# PotyEEG_v9.net
KiCad netlist of a schematic drawn in EAGLE
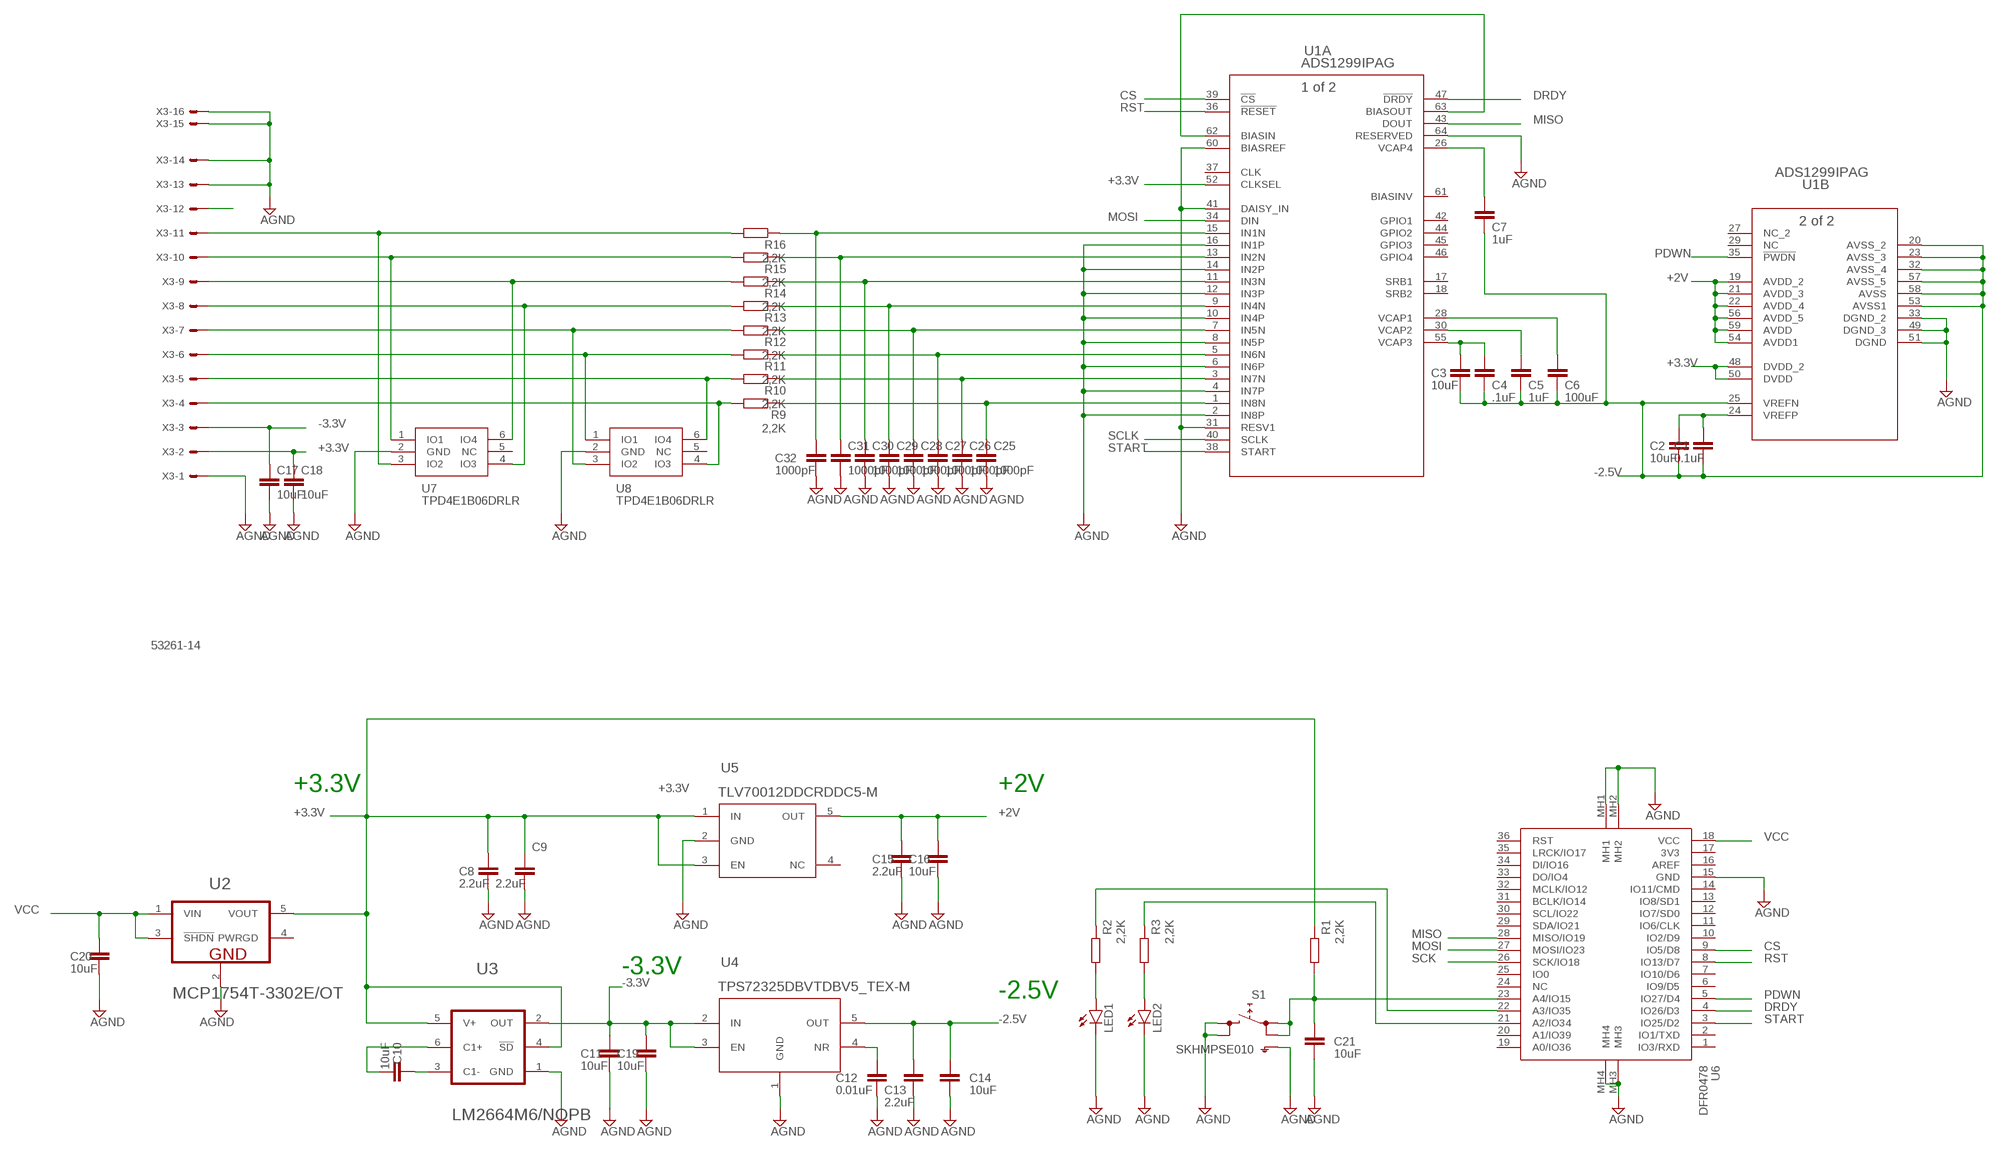
[diagram p0: schematic, sheet 1]

(export (version "E")
  (design (tool "Eeschema 10.0.6"))
  (components
    (comp (ref "C1")
      (value "0.1uF")
      (footprint "eagle-import:C0805K")
      (libsource (lib "eagle-import") (part "C-EUC0805K"))
    )
    (comp (ref "C2")
      (value "10uF")
      (footprint "eagle-import:C0805K")
      (libsource (lib "eagle-import") (part "C-EUC0805K"))
    )
    (comp (ref "C3")
      (value "10uF")
      (footprint "eagle-import:C0805K")
      (libsource (lib "eagle-import") (part "C-EUC0805K"))
    )
    (comp (ref "C4")
      (value ".1uF")
      (footprint "eagle-import:C0805K")
      (libsource (lib "eagle-import") (part "C-EUC0805K"))
    )
    (comp (ref "C5")
      (value "1uF")
      (footprint "eagle-import:C0805K")
      (libsource (lib "eagle-import") (part "C-EUC0805K"))
    )
    (comp (ref "C6")
      (value "100uF")
      (footprint "eagle-import:C0805K")
      (libsource (lib "eagle-import") (part "C-EUC0805K"))
    )
    (comp (ref "C7")
      (value "1uF")
      (footprint "eagle-import:C0805K")
      (libsource (lib "eagle-import") (part "C-EUC0805K"))
    )
    (comp (ref "C8")
      (value "2.2uF")
      (footprint "eagle-import:C0805K")
      (libsource (lib "eagle-import") (part "C-EUC0805K"))
    )
    (comp (ref "C9")
      (value "2.2uF")
      (footprint "eagle-import:C0805K")
      (libsource (lib "eagle-import") (part "C-EUC0805K"))
    )
    (comp (ref "C10")
      (value "10uF")
      (footprint "eagle-import:C0805K")
      (libsource (lib "eagle-import") (part "C-EUC0805K"))
    )
    (comp (ref "C11")
      (value "10uF")
      (footprint "eagle-import:C0805K")
      (libsource (lib "eagle-import") (part "C-EUC0805K"))
    )
    (comp (ref "C12")
      (value "0.01uF")
      (footprint "eagle-import:C0805K")
      (libsource (lib "eagle-import") (part "C-EUC0805K"))
    )
    (comp (ref "C13")
      (value "2.2uF")
      (footprint "eagle-import:C0805K")
      (libsource (lib "eagle-import") (part "C-EUC0805K"))
    )
    (comp (ref "C14")
      (value "10uF")
      (footprint "eagle-import:C0805K")
      (libsource (lib "eagle-import") (part "C-EUC0805K"))
    )
    (comp (ref "C15")
      (value "2.2uF")
      (footprint "eagle-import:C0805K")
      (libsource (lib "eagle-import") (part "C-EUC0805K"))
    )
    (comp (ref "C16")
      (value "10uF")
      (footprint "eagle-import:C0805K")
      (libsource (lib "eagle-import") (part "C-EUC0805K"))
    )
    (comp (ref "C17")
      (value "10uF")
      (footprint "eagle-import:C0603")
      (libsource (lib "eagle-import") (part "C-EUC0603"))
    )
    (comp (ref "C18")
      (value "10uF")
      (footprint "eagle-import:C0603")
      (libsource (lib "eagle-import") (part "C-EUC0603"))
    )
    (comp (ref "C19")
      (value "10uF")
      (footprint "eagle-import:C0805K")
      (libsource (lib "eagle-import") (part "C-EUC0805K"))
    )
    (comp (ref "C20")
      (value "10uF")
      (footprint "eagle-import:C0805K")
      (libsource (lib "eagle-import") (part "C-EUC0805K"))
    )
    (comp (ref "C21")
      (value "10uF")
      (footprint "eagle-import:C0805K")
      (libsource (lib "eagle-import") (part "C-EUC0805K"))
    )
    (comp (ref "C25")
      (value "1000pF")
      (footprint "eagle-import:C0603")
      (libsource (lib "eagle-import") (part "C-EUC0603"))
    )
    (comp (ref "C26")
      (value "1000pF")
      (footprint "eagle-import:C0603")
      (libsource (lib "eagle-import") (part "C-EUC0603"))
    )
    (comp (ref "C27")
      (value "1000pF")
      (footprint "eagle-import:C0603")
      (libsource (lib "eagle-import") (part "C-EUC0603"))
    )
    (comp (ref "C28")
      (value "1000pF")
      (footprint "eagle-import:C0603")
      (libsource (lib "eagle-import") (part "C-EUC0603"))
    )
    (comp (ref "C29")
      (value "1000pF")
      (footprint "eagle-import:C0603")
      (libsource (lib "eagle-import") (part "C-EUC0603"))
    )
    (comp (ref "C30")
      (value "1000pF")
      (footprint "eagle-import:C0603")
      (libsource (lib "eagle-import") (part "C-EUC0603"))
    )
    (comp (ref "C31")
      (value "1000pF")
      (footprint "eagle-import:C0603")
      (libsource (lib "eagle-import") (part "C-EUC0603"))
    )
    (comp (ref "C32")
      (value "1000pF")
      (footprint "eagle-import:C0603")
      (libsource (lib "eagle-import") (part "C-EUC0603"))
    )
    (comp (ref "LED1")
      (value "LEDSML0805")
      (footprint "eagle-import:SML0805")
      (libsource (lib "eagle-import") (part "LEDSML0805"))
    )
    (comp (ref "LED2")
      (value "LEDSML0805")
      (footprint "eagle-import:SML0805")
      (libsource (lib "eagle-import") (part "LEDSML0805"))
    )
    (comp (ref "R1")
      (value "2,2K")
      (footprint "eagle-import:R0603")
      (libsource (lib "eagle-import") (part "R-EU_R0603"))
    )
    (comp (ref "R2")
      (value "2,2K")
      (footprint "eagle-import:R0603")
      (libsource (lib "eagle-import") (part "R-EU_R0603"))
    )
    (comp (ref "R3")
      (value "2,2K")
      (footprint "eagle-import:R0603")
      (libsource (lib "eagle-import") (part "R-EU_R0603"))
    )
    (comp (ref "R9")
      (value "2,2K")
      (footprint "eagle-import:R0603")
      (libsource (lib "eagle-import") (part "R-EU_R0603"))
    )
    (comp (ref "R10")
      (value "2,2K")
      (footprint "eagle-import:R0603")
      (libsource (lib "eagle-import") (part "R-EU_R0603"))
    )
    (comp (ref "R11")
      (value "2,2K")
      (footprint "eagle-import:R0603")
      (libsource (lib "eagle-import") (part "R-EU_R0603"))
    )
    (comp (ref "R12")
      (value "2,2K")
      (footprint "eagle-import:R0603")
      (libsource (lib "eagle-import") (part "R-EU_R0603"))
    )
    (comp (ref "R13")
      (value "2,2K")
      (footprint "eagle-import:R0603")
      (libsource (lib "eagle-import") (part "R-EU_R0603"))
    )
    (comp (ref "R14")
      (value "2,2K")
      (footprint "eagle-import:R0603")
      (libsource (lib "eagle-import") (part "R-EU_R0603"))
    )
    (comp (ref "R15")
      (value "2,2K")
      (footprint "eagle-import:R0603")
      (libsource (lib "eagle-import") (part "R-EU_R0603"))
    )
    (comp (ref "R16")
      (value "2,2K")
      (footprint "eagle-import:R0603")
      (libsource (lib "eagle-import") (part "R-EU_R0603"))
    )
    (comp (ref "S1")
      (value "SKHMPSE010")
      (footprint "eagle-import:SKHMPXE010")
      (libsource (lib "eagle-import") (part "SKHMPE010S"))
    )
    (comp (ref "U1")
      (value "ADS1299IPAG")
      (footprint "eagle-import:PAG64_TEX")
      (libsource (lib "eagle-import") (part "ADS1299IPAG"))
    )
    (comp (ref "U2")
      (value "MICROCHIP_MCP1754T-3302E-OTMICROCHIP_MCP1754T-3302E-OT_0_1")
      (footprint "eagle-import:MICROCHIP_MCP1754T-3302E-OT_1")
      (fields (field (name "MF") "Microchip") (field (name "MPN") "MCP1754T-3302E/OT"))
      (libsource (lib "eagle-import") (part "MICROCHIP_MCP1754T-3302E-OTMICROCHIP_MCP1754T-3302E-OT_0_1"))
    )
    (comp (ref "U3")
      (value "TEXAS_INSTRUMENTS_LM2664M6-NOPBTEXAS_INSTRUMENTS_LM2664M6-NOPB_0_2")
      (footprint "eagle-import:TEXAS_INSTRUMENTS_LM2664M6-NOPB_2")
      (fields (field (name "MF") "Texas Instruments") (field (name "MPN") "LM2664M6/NOPB"))
      (libsource (lib "eagle-import") (part "TEXAS_INSTRUMENTS_LM2664M6-NOPBTEXAS_INSTRUMENTS_LM2664M6-NOPB_0_2"))
    )
    (comp (ref "U4")
      (value "TPS72325DBVTDBV5_TEX-M")
      (footprint "eagle-import:DBV5_TEX-M")
      (fields
        (field (name "MANUFACTURER") "Texas Instruments")
        (field (name "MANUFACTURER_PART_NUMBER") "TPS72325DBVT")
      )
      (libsource (lib "eagle-import") (part "TPS72325DBVTDBV5_TEX-M"))
    )
    (comp (ref "U5")
      (value "TLV70012DDCRDDC5-M")
      (footprint "eagle-import:DDC5-M")
      (fields
        (field (name "GENERIC_PART_NUMBER") "TLV70012")
        (field (name "MANUFACTURER") "Texas Instruments")
        (field (name "MANUFACTURER_PART_NUMBER") "TLV70012DDCR")
      )
      (libsource (lib "eagle-import") (part "TLV70012DDCRDDC5-M"))
    )
    (comp (ref "U6")
      (value "DFR0478")
      (footprint "eagle-import:FIREBEETLE_ESP32")
      (fields (field (name "MOUSER_PART_NUMBER") "426-DFR0478"))
      (libsource (lib "eagle-import") (part "DFR0478"))
    )
    (comp (ref "U7")
      (value "TPD4E1B06DRLR")
      (footprint "eagle-import:SOP50P160X60-6N")
      (fields (field (name "MOUSER_PART_NUMBER") "595-TPD4E1B06DRLR"))
      (libsource (lib "eagle-import") (part "TPD4E1B06DRLR"))
    )
    (comp (ref "U8")
      (value "TPD4E1B06DRLR")
      (footprint "eagle-import:SOP50P160X60-6N")
      (fields (field (name "MOUSER_PART_NUMBER") "595-TPD4E1B06DRLR"))
      (libsource (lib "eagle-import") (part "TPD4E1B06DRLR"))
    )
    (comp (ref "X3")
      (value "53261-14")
      (footprint "eagle-import:53261-14")
      (fields (field (name "MF") "MOLEX"))
      (libsource (lib "eagle-import") (part "53?-14261"))
    )
  )
  (nets
    (net (code "1") (name "/+2V") (class "Default")
      (node (ref "C15") (pin "1") (pinfunction "1_1") (pintype "passive"))
      (node (ref "C16") (pin "1") (pinfunction "1_1") (pintype "passive"))
      (node (ref "U1") (pin "19") (pinfunction "AVDD_2_19") (pintype "power_in"))
      (node (ref "U1") (pin "21") (pinfunction "AVDD_3_21") (pintype "power_in"))
      (node (ref "U1") (pin "22") (pinfunction "AVDD_4_22") (pintype "power_in"))
      (node (ref "U1") (pin "54") (pinfunction "AVDD1_54") (pintype "power_in"))
      (node (ref "U1") (pin "56") (pinfunction "AVDD_5_56") (pintype "power_in"))
      (node (ref "U1") (pin "59") (pinfunction "AVDD_59") (pintype "power_in"))
      (node (ref "U5") (pin "5") (pinfunction "OUT_5") (pintype "output"))
    )
    (net (code "2") (name "/+3.3V") (class "Default")
      (node (ref "C18") (pin "1") (pinfunction "1_1") (pintype "passive"))
      (node (ref "C8") (pin "1") (pinfunction "1_1") (pintype "passive"))
      (node (ref "C9") (pin "1") (pinfunction "1_1") (pintype "passive"))
      (node (ref "R1") (pin "1") (pinfunction "1_1") (pintype "passive"))
      (node (ref "U1") (pin "48") (pinfunction "DVDD_2_48") (pintype "power_in"))
      (node (ref "U1") (pin "50") (pinfunction "DVDD_50") (pintype "power_in"))
      (node (ref "U1") (pin "52") (pinfunction "CLKSEL_52") (pintype "input"))
      (node (ref "U2") (pin "5") (pinfunction "VOUT_5") (pintype "power_in"))
      (node (ref "U3") (pin "4") (pinfunction "~{SD}_4") (pintype "input"))
      (node (ref "U3") (pin "5") (pinfunction "V+_5") (pintype "power_in"))
      (node (ref "U5") (pin "1") (pinfunction "IN_1") (pintype "input"))
      (node (ref "U5") (pin "3") (pinfunction "EN_3") (pintype "passive"))
      (node (ref "X3") (pin "2") (pinfunction "S_2") (pintype "passive"))
    )
    (net (code "3") (name "/-2.5V") (class "Default")
      (node (ref "C1") (pin "2") (pinfunction "2_2") (pintype "passive"))
      (node (ref "C13") (pin "1") (pinfunction "1_1") (pintype "passive"))
      (node (ref "C14") (pin "1") (pinfunction "1_1") (pintype "passive"))
      (node (ref "C2") (pin "2") (pinfunction "2_2") (pintype "passive"))
      (node (ref "C3") (pin "2") (pinfunction "2_2") (pintype "passive"))
      (node (ref "C4") (pin "2") (pinfunction "2_2") (pintype "passive"))
      (node (ref "C5") (pin "2") (pinfunction "2_2") (pintype "passive"))
      (node (ref "C6") (pin "2") (pinfunction "2_2") (pintype "passive"))
      (node (ref "C7") (pin "2") (pinfunction "2_2") (pintype "passive"))
      (node (ref "U1") (pin "20") (pinfunction "AVSS_2_20") (pintype "power_in"))
      (node (ref "U1") (pin "23") (pinfunction "AVSS_3_23") (pintype "power_in"))
      (node (ref "U1") (pin "25") (pinfunction "VREFN_25") (pintype "input"))
      (node (ref "U1") (pin "32") (pinfunction "AVSS_4_32") (pintype "power_in"))
      (node (ref "U1") (pin "53") (pinfunction "AVSS1_53") (pintype "power_in"))
      (node (ref "U1") (pin "57") (pinfunction "AVSS_5_57") (pintype "power_in"))
      (node (ref "U1") (pin "58") (pinfunction "AVSS_58") (pintype "power_in"))
      (node (ref "U4") (pin "5") (pinfunction "OUT_5") (pintype "output"))
    )
    (net (code "4") (name "/-3.3V") (class "Default")
      (node (ref "C11") (pin "1") (pinfunction "1_1") (pintype "passive"))
      (node (ref "C17") (pin "1") (pinfunction "1_1") (pintype "passive"))
      (node (ref "C19") (pin "1") (pinfunction "1_1") (pintype "passive"))
      (node (ref "U3") (pin "2") (pinfunction "OUT_2") (pintype "power_in"))
      (node (ref "U4") (pin "2") (pinfunction "IN_2") (pintype "input"))
      (node (ref "U4") (pin "3") (pinfunction "EN_3") (pintype "passive"))
      (node (ref "X3") (pin "3") (pinfunction "S_3") (pintype "passive"))
    )
    (net (code "5") (name "/CS") (class "Default")
      (node (ref "U1") (pin "39") (pinfunction "~{CS}_39") (pintype "input"))
      (node (ref "U6") (pin "9") (pinfunction "IO5/D8_9") (pintype "bidirectional"))
    )
    (net (code "6") (name "/DRDY") (class "Default")
      (node (ref "U1") (pin "47") (pinfunction "~{DRDY}_47") (pintype "output"))
      (node (ref "U6") (pin "4") (pinfunction "IO26/D3_4") (pintype "bidirectional"))
    )
    (net (code "7") (name "/MISO") (class "Default")
      (node (ref "U1") (pin "43") (pinfunction "DOUT_43") (pintype "output"))
      (node (ref "U6") (pin "28") (pinfunction "MISO/IO19_28") (pintype "bidirectional"))
    )
    (net (code "8") (name "/MOSI") (class "Default")
      (node (ref "U1") (pin "34") (pinfunction "DIN_34") (pintype "input"))
      (node (ref "U6") (pin "27") (pinfunction "MOSI/IO23_27") (pintype "bidirectional"))
    )
    (net (code "9") (name "/PDWN") (class "Default")
      (node (ref "U1") (pin "35") (pinfunction "~{PWDN}_35") (pintype "power_in"))
      (node (ref "U6") (pin "5") (pinfunction "IO27/D4_5") (pintype "bidirectional"))
    )
    (net (code "10") (name "/RST") (class "Default")
      (node (ref "U1") (pin "36") (pinfunction "~{RESET}_36") (pintype "input"))
      (node (ref "U6") (pin "8") (pinfunction "IO13/D7_8") (pintype "bidirectional"))
    )
    (net (code "11") (name "/SCK") (class "Default")
      (node (ref "U6") (pin "26") (pinfunction "SCK/IO18_26") (pintype "bidirectional"))
    )
    (net (code "12") (name "/SCLK") (class "Default")
      (node (ref "U1") (pin "40") (pinfunction "SCLK_40") (pintype "input"))
    )
    (net (code "13") (name "/START") (class "Default")
      (node (ref "U1") (pin "38") (pinfunction "START_38") (pintype "input"))
      (node (ref "U6") (pin "3") (pinfunction "IO25/D2_3") (pintype "bidirectional"))
    )
    (net (code "14") (name "/VCC") (class "Default")
      (node (ref "C20") (pin "1") (pinfunction "1_1") (pintype "passive"))
      (node (ref "U2") (pin "1") (pinfunction "VIN_1") (pintype "power_in"))
      (node (ref "U2") (pin "3") (pinfunction "~{SHDN}_3") (pintype "input"))
      (node (ref "U6") (pin "18") (pinfunction "VCC_18") (pintype "bidirectional"))
    )
    (net (code "15") (name "AGND") (class "Default")
      (node (ref "C11") (pin "2") (pinfunction "2_2") (pintype "passive"))
      (node (ref "C12") (pin "2") (pinfunction "2_2") (pintype "passive"))
      (node (ref "C13") (pin "2") (pinfunction "2_2") (pintype "passive"))
      (node (ref "C14") (pin "2") (pinfunction "2_2") (pintype "passive"))
      (node (ref "C15") (pin "2") (pinfunction "2_2") (pintype "passive"))
      (node (ref "C16") (pin "2") (pinfunction "2_2") (pintype "passive"))
      (node (ref "C17") (pin "2") (pinfunction "2_2") (pintype "passive"))
      (node (ref "C18") (pin "2") (pinfunction "2_2") (pintype "passive"))
      (node (ref "C19") (pin "2") (pinfunction "2_2") (pintype "passive"))
      (node (ref "C20") (pin "2") (pinfunction "2_2") (pintype "passive"))
      (node (ref "C21") (pin "2") (pinfunction "2_2") (pintype "passive"))
      (node (ref "C25") (pin "2") (pinfunction "2_2") (pintype "passive"))
      (node (ref "C26") (pin "2") (pinfunction "2_2") (pintype "passive"))
      (node (ref "C27") (pin "2") (pinfunction "2_2") (pintype "passive"))
      (node (ref "C28") (pin "2") (pinfunction "2_2") (pintype "passive"))
      (node (ref "C29") (pin "2") (pinfunction "2_2") (pintype "passive"))
      (node (ref "C30") (pin "2") (pinfunction "2_2") (pintype "passive"))
      (node (ref "C31") (pin "2") (pinfunction "2_2") (pintype "passive"))
      (node (ref "C32") (pin "2") (pinfunction "2_2") (pintype "passive"))
      (node (ref "C8") (pin "2") (pinfunction "2_2") (pintype "passive"))
      (node (ref "C9") (pin "2") (pinfunction "2_2") (pintype "passive"))
      (node (ref "LED1") (pin "C") (pinfunction "C_C") (pintype "passive"))
      (node (ref "LED2") (pin "C") (pinfunction "C_C") (pintype "passive"))
      (node (ref "S1") (pin "3") (pinfunction "2.1_3") (pintype "passive"))
      (node (ref "S1") (pin "4") (pinfunction "2.2_4") (pintype "passive"))
      (node (ref "S1") (pin "5") (pinfunction "SH_5") (pintype "passive"))
      (node (ref "U1") (pin "10") (pinfunction "IN4P_10") (pintype "input"))
      (node (ref "U1") (pin "12") (pinfunction "IN3P_12") (pintype "input"))
      (node (ref "U1") (pin "14") (pinfunction "IN2P_14") (pintype "input"))
      (node (ref "U1") (pin "16") (pinfunction "IN1P_16") (pintype "input"))
      (node (ref "U1") (pin "2") (pinfunction "IN8P_2") (pintype "input"))
      (node (ref "U1") (pin "31") (pinfunction "RESV1_31") (pintype "input"))
      (node (ref "U1") (pin "33") (pinfunction "DGND_2_33") (pintype "power_in"))
      (node (ref "U1") (pin "4") (pinfunction "IN7P_4") (pintype "input"))
      (node (ref "U1") (pin "41") (pinfunction "DAISY_IN_41") (pintype "input"))
      (node (ref "U1") (pin "49") (pinfunction "DGND_3_49") (pintype "power_in"))
      (node (ref "U1") (pin "51") (pinfunction "DGND_51") (pintype "power_in"))
      (node (ref "U1") (pin "6") (pinfunction "IN6P_6") (pintype "input"))
      (node (ref "U1") (pin "60") (pinfunction "BIASREF_60") (pintype "input"))
      (node (ref "U1") (pin "64") (pinfunction "RESERVED_64") (pintype "output"))
      (node (ref "U1") (pin "8") (pinfunction "IN5P_8") (pintype "input"))
      (node (ref "U2") (pin "2") (pinfunction "GND_2") (pintype "power_in"))
      (node (ref "U3") (pin "1") (pinfunction "GND_1") (pintype "power_in"))
      (node (ref "U4") (pin "1") (pinfunction "GND_1") (pintype "power_in"))
      (node (ref "U5") (pin "2") (pinfunction "GND_2") (pintype "power_in"))
      (node (ref "U6") (pin "15") (pinfunction "GND_15") (pintype "bidirectional"))
      (node (ref "U6") (pin "MH1") (pinfunction "MH1_MH1") (pintype "bidirectional"))
      (node (ref "U6") (pin "MH2") (pinfunction "MH2_MH2") (pintype "bidirectional"))
      (node (ref "U6") (pin "MH3") (pinfunction "MH3_MH3") (pintype "bidirectional"))
      (node (ref "U6") (pin "MH4") (pinfunction "MH4_MH4") (pintype "bidirectional"))
      (node (ref "U7") (pin "2") (pinfunction "GND_2") (pintype "bidirectional"))
      (node (ref "U8") (pin "2") (pinfunction "GND_2") (pintype "bidirectional"))
      (node (ref "X3") (pin "1") (pinfunction "S_1") (pintype "passive"))
      (node (ref "X3") (pin "13") (pinfunction "S_13") (pintype "passive"))
      (node (ref "X3") (pin "14") (pinfunction "S_14") (pintype "passive"))
      (node (ref "X3") (pin "S1") (pinfunction "S_S1") (pintype "passive"))
      (node (ref "X3") (pin "S2") (pinfunction "S_S2") (pintype "passive"))
    )
    (net (code "16") (name "Net-(LED1-PadA)") (class "Default")
      (node (ref "LED1") (pin "A") (pinfunction "A_A") (pintype "passive"))
      (node (ref "R2") (pin "2") (pinfunction "2_2") (pintype "passive"))
    )
    (net (code "17") (name "Net-(LED2-PadA)") (class "Default")
      (node (ref "LED2") (pin "A") (pinfunction "A_A") (pintype "passive"))
      (node (ref "R3") (pin "2") (pinfunction "2_2") (pintype "passive"))
    )
    (net (code "18") (name "Net-(S1-1.1)") (class "Default")
      (node (ref "C21") (pin "1") (pinfunction "1_1") (pintype "passive"))
      (node (ref "R1") (pin "2") (pinfunction "2_2") (pintype "passive"))
      (node (ref "S1") (pin "1") (pinfunction "1.1_1") (pintype "passive"))
      (node (ref "S1") (pin "2") (pinfunction "1.2_2") (pintype "passive"))
      (node (ref "U6") (pin "23") (pinfunction "A4/IO15_23") (pintype "bidirectional"))
    )
    (net (code "19") (name "Net-(U1A-BIASIN)") (class "Default")
      (node (ref "U1") (pin "62") (pinfunction "BIASIN_62") (pintype "input"))
      (node (ref "U1") (pin "63") (pinfunction "BIASOUT_63") (pintype "output"))
    )
    (net (code "20") (name "Net-(U1A-IN1N)") (class "Default")
      (node (ref "C32") (pin "1") (pinfunction "1_1") (pintype "passive"))
      (node (ref "R16") (pin "1") (pinfunction "1_1") (pintype "passive"))
      (node (ref "U1") (pin "15") (pinfunction "IN1N_15") (pintype "input"))
    )
    (net (code "21") (name "Net-(U1A-IN2N)") (class "Default")
      (node (ref "C31") (pin "1") (pinfunction "1_1") (pintype "passive"))
      (node (ref "R15") (pin "1") (pinfunction "1_1") (pintype "passive"))
      (node (ref "U1") (pin "13") (pinfunction "IN2N_13") (pintype "input"))
    )
    (net (code "22") (name "Net-(U1A-IN3N)") (class "Default")
      (node (ref "C30") (pin "1") (pinfunction "1_1") (pintype "passive"))
      (node (ref "R14") (pin "1") (pinfunction "1_1") (pintype "passive"))
      (node (ref "U1") (pin "11") (pinfunction "IN3N_11") (pintype "input"))
    )
    (net (code "23") (name "Net-(U1A-IN4N)") (class "Default")
      (node (ref "C29") (pin "1") (pinfunction "1_1") (pintype "passive"))
      (node (ref "R13") (pin "1") (pinfunction "1_1") (pintype "passive"))
      (node (ref "U1") (pin "9") (pinfunction "IN4N_9") (pintype "input"))
    )
    (net (code "24") (name "Net-(U1A-IN5N)") (class "Default")
      (node (ref "C28") (pin "1") (pinfunction "1_1") (pintype "passive"))
      (node (ref "R12") (pin "1") (pinfunction "1_1") (pintype "passive"))
      (node (ref "U1") (pin "7") (pinfunction "IN5N_7") (pintype "input"))
    )
    (net (code "25") (name "Net-(U1A-IN6N)") (class "Default")
      (node (ref "C27") (pin "1") (pinfunction "1_1") (pintype "passive"))
      (node (ref "R11") (pin "1") (pinfunction "1_1") (pintype "passive"))
      (node (ref "U1") (pin "5") (pinfunction "IN6N_5") (pintype "input"))
    )
    (net (code "26") (name "Net-(U1A-IN7N)") (class "Default")
      (node (ref "C26") (pin "1") (pinfunction "1_1") (pintype "passive"))
      (node (ref "R10") (pin "1") (pinfunction "1_1") (pintype "passive"))
      (node (ref "U1") (pin "3") (pinfunction "IN7N_3") (pintype "input"))
    )
    (net (code "27") (name "Net-(U1A-IN8N)") (class "Default")
      (node (ref "C25") (pin "1") (pinfunction "1_1") (pintype "passive"))
      (node (ref "R9") (pin "1") (pinfunction "1_1") (pintype "passive"))
      (node (ref "U1") (pin "1") (pinfunction "IN8N_1") (pintype "input"))
    )
    (net (code "28") (name "Net-(U1A-VCAP1)") (class "Default")
      (node (ref "C6") (pin "1") (pinfunction "1_1") (pintype "passive"))
      (node (ref "U1") (pin "28") (pinfunction "VCAP1_28") (pintype "passive"))
    )
    (net (code "29") (name "Net-(U1A-VCAP2)") (class "Default")
      (node (ref "C5") (pin "1") (pinfunction "1_1") (pintype "passive"))
      (node (ref "U1") (pin "30") (pinfunction "VCAP2_30") (pintype "passive"))
    )
    (net (code "30") (name "Net-(U1A-VCAP3)") (class "Default")
      (node (ref "C3") (pin "1") (pinfunction "1_1") (pintype "passive"))
      (node (ref "C4") (pin "1") (pinfunction "1_1") (pintype "passive"))
      (node (ref "U1") (pin "55") (pinfunction "VCAP3_55") (pintype "passive"))
    )
    (net (code "31") (name "Net-(U1A-VCAP4)") (class "Default")
      (node (ref "C7") (pin "1") (pinfunction "1_1") (pintype "passive"))
      (node (ref "U1") (pin "26") (pinfunction "VCAP4_26") (pintype "output"))
    )
    (net (code "32") (name "Net-(U1B-VREFP)") (class "Default")
      (node (ref "C1") (pin "1") (pinfunction "1_1") (pintype "passive"))
      (node (ref "C2") (pin "1") (pinfunction "1_1") (pintype "passive"))
      (node (ref "U1") (pin "24") (pinfunction "VREFP_24") (pintype "bidirectional"))
    )
    (net (code "33") (name "Net-(U3-C1+)") (class "Default")
      (node (ref "C10") (pin "2") (pinfunction "2_2") (pintype "passive"))
      (node (ref "U3") (pin "6") (pinfunction "C1+_6") (pintype "input"))
    )
    (net (code "34") (name "Net-(U3-C1-)") (class "Default")
      (node (ref "C10") (pin "1") (pinfunction "1_1") (pintype "passive"))
      (node (ref "U3") (pin "3") (pinfunction "C1-_3") (pintype "input"))
    )
    (net (code "35") (name "Net-(U4-NR)") (class "Default")
      (node (ref "C12") (pin "1") (pinfunction "1_1") (pintype "passive"))
      (node (ref "U4") (pin "4") (pinfunction "NR_4") (pintype "passive"))
    )
    (net (code "36") (name "Net-(U6-A2{slash}IO34)") (class "Default")
      (node (ref "R3") (pin "1") (pinfunction "1_1") (pintype "passive"))
      (node (ref "U6") (pin "21") (pinfunction "A2/IO34_21") (pintype "bidirectional"))
    )
    (net (code "37") (name "Net-(U6-A3{slash}IO35)") (class "Default")
      (node (ref "R2") (pin "1") (pinfunction "1_1") (pintype "passive"))
      (node (ref "U6") (pin "22") (pinfunction "A3/IO35_22") (pintype "bidirectional"))
    )
    (net (code "38") (name "Net-(U7-IO1)") (class "Default")
      (node (ref "R15") (pin "2") (pinfunction "2_2") (pintype "passive"))
      (node (ref "U7") (pin "1") (pinfunction "IO1_1") (pintype "bidirectional"))
      (node (ref "X3") (pin "10") (pinfunction "S_10") (pintype "passive"))
    )
    (net (code "39") (name "Net-(U7-IO2)") (class "Default")
      (node (ref "R16") (pin "2") (pinfunction "2_2") (pintype "passive"))
      (node (ref "U7") (pin "3") (pinfunction "IO2_3") (pintype "bidirectional"))
      (node (ref "X3") (pin "11") (pinfunction "S_11") (pintype "passive"))
    )
    (net (code "40") (name "Net-(U7-IO3)") (class "Default")
      (node (ref "R13") (pin "2") (pinfunction "2_2") (pintype "passive"))
      (node (ref "U7") (pin "4") (pinfunction "IO3_4") (pintype "bidirectional"))
      (node (ref "X3") (pin "8") (pinfunction "S_8") (pintype "passive"))
    )
    (net (code "41") (name "Net-(U7-IO4)") (class "Default")
      (node (ref "R14") (pin "2") (pinfunction "2_2") (pintype "passive"))
      (node (ref "U7") (pin "6") (pinfunction "IO4_6") (pintype "bidirectional"))
      (node (ref "X3") (pin "9") (pinfunction "S_9") (pintype "passive"))
    )
    (net (code "42") (name "Net-(U8-IO1)") (class "Default")
      (node (ref "R11") (pin "2") (pinfunction "2_2") (pintype "passive"))
      (node (ref "U8") (pin "1") (pinfunction "IO1_1") (pintype "bidirectional"))
      (node (ref "X3") (pin "6") (pinfunction "S_6") (pintype "passive"))
    )
    (net (code "43") (name "Net-(U8-IO2)") (class "Default")
      (node (ref "R12") (pin "2") (pinfunction "2_2") (pintype "passive"))
      (node (ref "U8") (pin "3") (pinfunction "IO2_3") (pintype "bidirectional"))
      (node (ref "X3") (pin "7") (pinfunction "S_7") (pintype "passive"))
    )
    (net (code "44") (name "Net-(U8-IO3)") (class "Default")
      (node (ref "R9") (pin "2") (pinfunction "2_2") (pintype "passive"))
      (node (ref "U8") (pin "4") (pinfunction "IO3_4") (pintype "bidirectional"))
      (node (ref "X3") (pin "4") (pinfunction "S_4") (pintype "passive"))
    )
    (net (code "45") (name "Net-(U8-IO4)") (class "Default")
      (node (ref "R10") (pin "2") (pinfunction "2_2") (pintype "passive"))
      (node (ref "U8") (pin "6") (pinfunction "IO4_6") (pintype "bidirectional"))
      (node (ref "X3") (pin "5") (pinfunction "S_5") (pintype "passive"))
    )
    (net (code "46") (name "unconnected-(U1A-BIASINV-Pad61)") (class "Default")
      (node (ref "U1") (pin "61") (pinfunction "BIASINV_61") (pintype "bidirectional"))
    )
    (net (code "47") (name "unconnected-(U1A-CLK-Pad37)") (class "Default")
      (node (ref "U1") (pin "37") (pinfunction "CLK_37") (pintype "input"))
    )
    (net (code "48") (name "unconnected-(U1A-GPIO1-Pad42)") (class "Default")
      (node (ref "U1") (pin "42") (pinfunction "GPIO1_42") (pintype "bidirectional"))
    )
    (net (code "49") (name "unconnected-(U1A-GPIO2-Pad44)") (class "Default")
      (node (ref "U1") (pin "44") (pinfunction "GPIO2_44") (pintype "bidirectional"))
    )
    (net (code "50") (name "unconnected-(U1A-GPIO3-Pad45)") (class "Default")
      (node (ref "U1") (pin "45") (pinfunction "GPIO3_45") (pintype "bidirectional"))
    )
    (net (code "51") (name "unconnected-(U1A-GPIO4-Pad46)") (class "Default")
      (node (ref "U1") (pin "46") (pinfunction "GPIO4_46") (pintype "bidirectional"))
    )
    (net (code "52") (name "unconnected-(U1A-SRB1-Pad17)") (class "Default")
      (node (ref "U1") (pin "17") (pinfunction "SRB1_17") (pintype "bidirectional"))
    )
    (net (code "53") (name "unconnected-(U1A-SRB2-Pad18)") (class "Default")
      (node (ref "U1") (pin "18") (pinfunction "SRB2_18") (pintype "bidirectional"))
    )
    (net (code "54") (name "unconnected-(U1B-NC-Pad29)") (class "Default")
      (node (ref "U1") (pin "29") (pinfunction "NC_29") (pintype "no_connect"))
    )
    (net (code "55") (name "unconnected-(U1B-NC_2-Pad27)") (class "Default")
      (node (ref "U1") (pin "27") (pinfunction "NC_2_27") (pintype "no_connect"))
    )
    (net (code "56") (name "unconnected-(U2-PWRGD-Pad4)") (class "Default")
      (node (ref "U2") (pin "4") (pinfunction "PWRGD_4") (pintype "open_collector"))
    )
    (net (code "57") (name "unconnected-(U5-NC-Pad4)") (class "Default")
      (node (ref "U5") (pin "4") (pinfunction "NC_4") (pintype "passive"))
    )
    (net (code "58") (name "unconnected-(U6-3V3-Pad17)") (class "Default")
      (node (ref "U6") (pin "17") (pinfunction "3V3_17") (pintype "bidirectional"))
    )
    (net (code "59") (name "unconnected-(U6-A0{slash}IO36-Pad19)") (class "Default")
      (node (ref "U6") (pin "19") (pinfunction "A0/IO36_19") (pintype "bidirectional"))
    )
    (net (code "60") (name "unconnected-(U6-A1{slash}IO39-Pad20)") (class "Default")
      (node (ref "U6") (pin "20") (pinfunction "A1/IO39_20") (pintype "bidirectional"))
    )
    (net (code "61") (name "unconnected-(U6-AREF-Pad16)") (class "Default")
      (node (ref "U6") (pin "16") (pinfunction "AREF_16") (pintype "bidirectional"))
    )
    (net (code "62") (name "unconnected-(U6-BCLK{slash}IO14-Pad31)") (class "Default")
      (node (ref "U6") (pin "31") (pinfunction "BCLK/IO14_31") (pintype "bidirectional"))
    )
    (net (code "63") (name "unconnected-(U6-DI{slash}IO16-Pad34)") (class "Default")
      (node (ref "U6") (pin "34") (pinfunction "DI/IO16_34") (pintype "bidirectional"))
    )
    (net (code "64") (name "unconnected-(U6-DO{slash}IO4-Pad33)") (class "Default")
      (node (ref "U6") (pin "33") (pinfunction "DO/IO4_33") (pintype "bidirectional"))
    )
    (net (code "65") (name "unconnected-(U6-IO0-Pad25)") (class "Default")
      (node (ref "U6") (pin "25") (pinfunction "IO0_25") (pintype "bidirectional"))
    )
    (net (code "66") (name "unconnected-(U6-IO1{slash}TXD-Pad2)") (class "Default")
      (node (ref "U6") (pin "2") (pinfunction "IO1/TXD_2") (pintype "bidirectional"))
    )
    (net (code "67") (name "unconnected-(U6-IO2{slash}D9-Pad10)") (class "Default")
      (node (ref "U6") (pin "10") (pinfunction "IO2/D9_10") (pintype "bidirectional"))
    )
    (net (code "68") (name "unconnected-(U6-IO3{slash}RXD-Pad1)") (class "Default")
      (node (ref "U6") (pin "1") (pinfunction "IO3/RXD_1") (pintype "bidirectional"))
    )
    (net (code "69") (name "unconnected-(U6-IO6{slash}CLK-Pad11)") (class "Default")
      (node (ref "U6") (pin "11") (pinfunction "IO6/CLK_11") (pintype "bidirectional"))
    )
    (net (code "70") (name "unconnected-(U6-IO7{slash}SD0-Pad12)") (class "Default")
      (node (ref "U6") (pin "12") (pinfunction "IO7/SD0_12") (pintype "bidirectional"))
    )
    (net (code "71") (name "unconnected-(U6-IO8{slash}SD1-Pad13)") (class "Default")
      (node (ref "U6") (pin "13") (pinfunction "IO8/SD1_13") (pintype "bidirectional"))
    )
    (net (code "72") (name "unconnected-(U6-IO9{slash}D5-Pad6)") (class "Default")
      (node (ref "U6") (pin "6") (pinfunction "IO9/D5_6") (pintype "bidirectional"))
    )
    (net (code "73") (name "unconnected-(U6-IO10{slash}D6-Pad7)") (class "Default")
      (node (ref "U6") (pin "7") (pinfunction "IO10/D6_7") (pintype "bidirectional"))
    )
    (net (code "74") (name "unconnected-(U6-IO11{slash}CMD-Pad14)") (class "Default")
      (node (ref "U6") (pin "14") (pinfunction "IO11/CMD_14") (pintype "bidirectional"))
    )
    (net (code "75") (name "unconnected-(U6-LRCK{slash}IO17-Pad35)") (class "Default")
      (node (ref "U6") (pin "35") (pinfunction "LRCK/IO17_35") (pintype "bidirectional"))
    )
    (net (code "76") (name "unconnected-(U6-MCLK{slash}IO12-Pad32)") (class "Default")
      (node (ref "U6") (pin "32") (pinfunction "MCLK/IO12_32") (pintype "bidirectional"))
    )
    (net (code "77") (name "unconnected-(U6-NC-Pad24)") (class "Default")
      (node (ref "U6") (pin "24") (pinfunction "NC_24") (pintype "no_connect"))
    )
    (net (code "78") (name "unconnected-(U6-RST-Pad36)") (class "Default")
      (node (ref "U6") (pin "36") (pinfunction "RST_36") (pintype "bidirectional"))
    )
    (net (code "79") (name "unconnected-(U6-SCL{slash}IO22-Pad30)") (class "Default")
      (node (ref "U6") (pin "30") (pinfunction "SCL/IO22_30") (pintype "bidirectional"))
    )
    (net (code "80") (name "unconnected-(U6-SDA{slash}IO21-Pad29)") (class "Default")
      (node (ref "U6") (pin "29") (pinfunction "SDA/IO21_29") (pintype "bidirectional"))
    )
    (net (code "81") (name "unconnected-(U7-NC-Pad5)") (class "Default")
      (node (ref "U7") (pin "5") (pinfunction "NC_5") (pintype "no_connect"))
    )
    (net (code "82") (name "unconnected-(U8-NC-Pad5)") (class "Default")
      (node (ref "U8") (pin "5") (pinfunction "NC_5") (pintype "no_connect"))
    )
    (net (code "83") (name "unconnected-(X3D-S-Pad12)") (class "Default")
      (node (ref "X3") (pin "12") (pinfunction "S_12") (pintype "passive"))
    )
  )
)
